# HW2.net
KiCad netlist of a schematic drawn in EAGLE
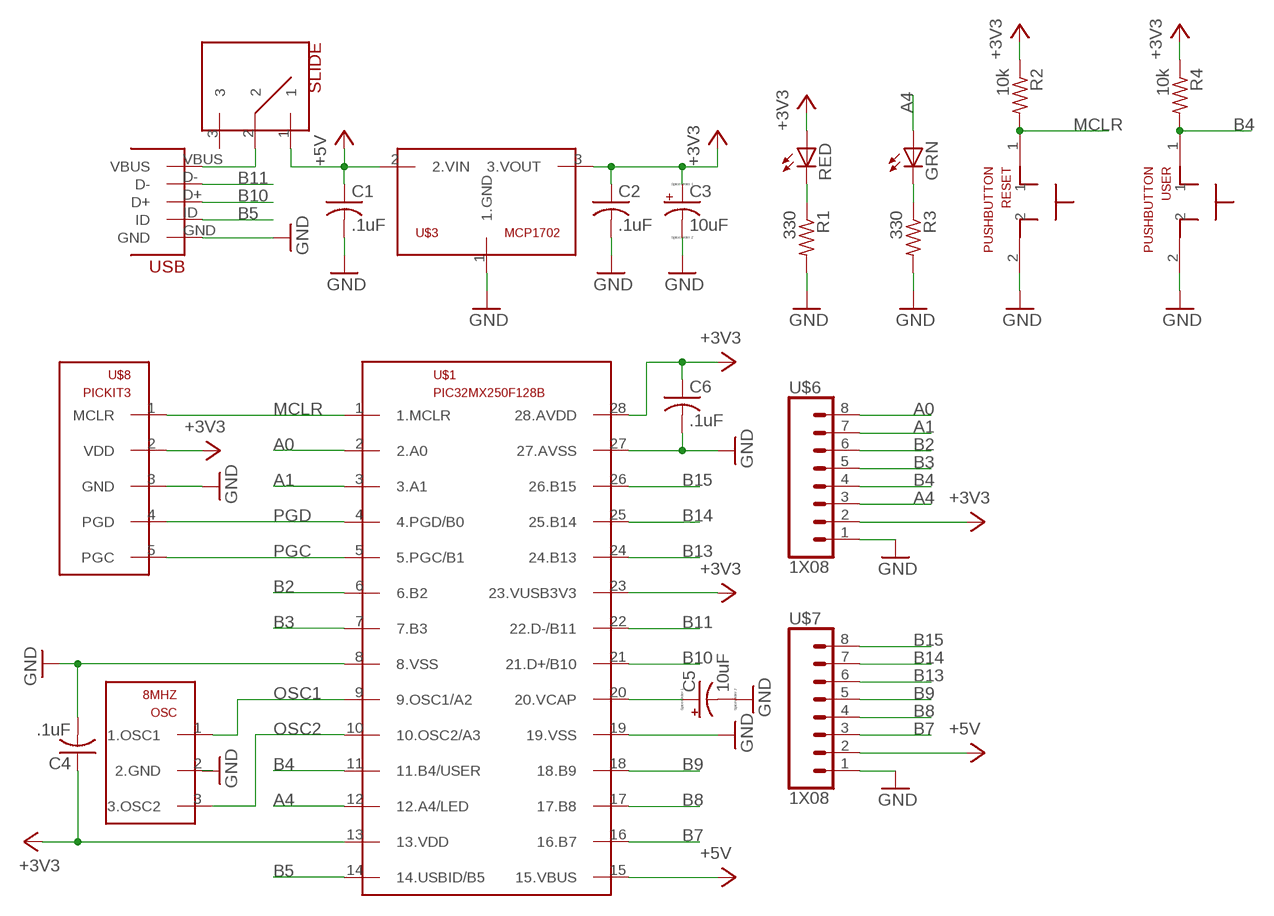
[diagram p0: schematic, sheet 1]

(export (version "E")
  (design (tool "Eeschema 10.0.6"))
  (components
    (comp (ref "8MHZ")
      (value "OSC")
      (footprint "eagle-import:OSC")
      (libsource (lib "eagle-import") (part "OSC"))
    )
    (comp (ref "C1")
      (value ".1uF")
      (footprint "eagle-import:C025-025X050")
      (libsource (lib "eagle-import") (part "C-US025-025X050"))
    )
    (comp (ref "C2")
      (value ".1uF")
      (footprint "eagle-import:C025-025X050")
      (libsource (lib "eagle-import") (part "C-US025-025X050"))
    )
    (comp (ref "C3")
      (value "10uF")
      (footprint "eagle-import:B45181B")
      (libsource (lib "eagle-import") (part "CPOL-USB45181B"))
    )
    (comp (ref "C4")
      (value ".1uF")
      (footprint "eagle-import:C025-025X050")
      (libsource (lib "eagle-import") (part "C-US025-025X050"))
    )
    (comp (ref "C5")
      (value "10uF")
      (footprint "eagle-import:B45181B")
      (libsource (lib "eagle-import") (part "CPOL-USB45181B"))
    )
    (comp (ref "C6")
      (value ".1uF")
      (footprint "eagle-import:C025-025X050")
      (libsource (lib "eagle-import") (part "C-US025-025X050"))
    )
    (comp (ref "GRN")
      (value "LED3MM")
      (footprint "eagle-import:LED3MM")
      (libsource (lib "eagle-import") (part "LED3MM"))
    )
    (comp (ref "R1")
      (value "330")
      (footprint "eagle-import:0207_10")
      (libsource (lib "eagle-import") (part "R-US_0207/10"))
    )
    (comp (ref "R2")
      (value "10k")
      (footprint "eagle-import:0207_10")
      (libsource (lib "eagle-import") (part "R-US_0207/10"))
    )
    (comp (ref "R3")
      (value "330")
      (footprint "eagle-import:0207_10")
      (libsource (lib "eagle-import") (part "R-US_0207/10"))
    )
    (comp (ref "R4")
      (value "10k")
      (footprint "eagle-import:0207_10")
      (libsource (lib "eagle-import") (part "R-US_0207/10"))
    )
    (comp (ref "RED")
      (value "LED3MM")
      (footprint "eagle-import:LED3MM")
      (libsource (lib "eagle-import") (part "LED3MM"))
    )
    (comp (ref "RESET")
      (value "PUSHBUTTON")
      (footprint "eagle-import:PUSHBUTTON")
      (libsource (lib "eagle-import") (part "PUSHBUTTON"))
    )
    (comp (ref "SLIDE")
      (value "SLIDESWITCH")
      (footprint "eagle-import:SLIDESWITCH")
      (libsource (lib "eagle-import") (part "SLIDESWITCH"))
    )
    (comp (ref "U$1")
      (value "PIC32MX250F128B")
      (footprint "eagle-import:DIL28-3")
      (libsource (lib "eagle-import") (part "PIC32MX250F128B"))
    )
    (comp (ref "U$3")
      (value "MCP1702")
      (footprint "eagle-import:TO92")
      (libsource (lib "eagle-import") (part "MCP1702"))
    )
    (comp (ref "U$5")
      (value "MINIUSB")
      (footprint "eagle-import:USB-MB-H")
      (libsource (lib "eagle-import") (part "MINIUSB"))
    )
    (comp (ref "U$6")
      (value "1X08")
      (footprint "eagle-import:CONN_08")
      (libsource (lib "eagle-import") (part "1X08"))
    )
    (comp (ref "U$7")
      (value "1X08")
      (footprint "eagle-import:CONN_08")
      (libsource (lib "eagle-import") (part "1X08"))
    )
    (comp (ref "U$8")
      (value "PICKIT3")
      (footprint "eagle-import:PICKIT3")
      (libsource (lib "eagle-import") (part "PICKIT3"))
    )
    (comp (ref "USER")
      (value "PUSHBUTTON")
      (footprint "eagle-import:PUSHBUTTON")
      (libsource (lib "eagle-import") (part "PUSHBUTTON"))
    )
  )
  (nets
    (net (code "1") (name "+3V3") (class "Default")
      (node (ref "C2") (pin "1") (pinfunction "1_1") (pintype "passive"))
      (node (ref "C3") (pin "+") (pinfunction "+_+") (pintype "passive"))
      (node (ref "C4") (pin "1") (pinfunction "1_1") (pintype "passive"))
      (node (ref "C6") (pin "1") (pinfunction "1_1") (pintype "passive"))
      (node (ref "R2") (pin "1") (pinfunction "1_1") (pintype "passive"))
      (node (ref "R4") (pin "1") (pinfunction "1_1") (pintype "passive"))
      (node (ref "RED") (pin "A") (pinfunction "A_A") (pintype "passive"))
      (node (ref "U$1") (pin "13") (pinfunction "13.VDD_13") (pintype "bidirectional"))
      (node (ref "U$1") (pin "23") (pinfunction "23.VUSB3V3_23") (pintype "bidirectional"))
      (node (ref "U$1") (pin "28") (pinfunction "28.AVDD_28") (pintype "bidirectional"))
      (node (ref "U$3") (pin "3") (pinfunction "3.VOUT_3") (pintype "bidirectional"))
      (node (ref "U$6") (pin "2") (pinfunction "2_2") (pintype "passive"))
      (node (ref "U$8") (pin "2") (pinfunction "VDD_2") (pintype "bidirectional"))
    )
    (net (code "2") (name "+5V") (class "Default")
      (node (ref "C1") (pin "1") (pinfunction "1_1") (pintype "passive"))
      (node (ref "SLIDE") (pin "1") (pinfunction "1_1") (pintype "bidirectional"))
      (node (ref "U$1") (pin "15") (pinfunction "15.VBUS_15") (pintype "bidirectional"))
      (node (ref "U$3") (pin "2") (pinfunction "2.VIN_2") (pintype "bidirectional"))
      (node (ref "U$7") (pin "2") (pinfunction "2_2") (pintype "passive"))
    )
    (net (code "3") (name "/A0") (class "Default")
      (node (ref "U$1") (pin "2") (pinfunction "2.A0_2") (pintype "bidirectional"))
      (node (ref "U$6") (pin "8") (pinfunction "8_8") (pintype "passive"))
    )
    (net (code "4") (name "/A1") (class "Default")
      (node (ref "U$1") (pin "3") (pinfunction "3.A1_3") (pintype "bidirectional"))
      (node (ref "U$6") (pin "7") (pinfunction "7_7") (pintype "passive"))
    )
    (net (code "5") (name "/A4") (class "Default")
      (node (ref "GRN") (pin "A") (pinfunction "A_A") (pintype "passive"))
      (node (ref "U$1") (pin "12") (pinfunction "12.A4/LED_12") (pintype "bidirectional"))
      (node (ref "U$6") (pin "3") (pinfunction "3_3") (pintype "passive"))
    )
    (net (code "6") (name "/B2") (class "Default")
      (node (ref "U$1") (pin "6") (pinfunction "6.B2_6") (pintype "bidirectional"))
      (node (ref "U$6") (pin "6") (pinfunction "6_6") (pintype "passive"))
    )
    (net (code "7") (name "/B3") (class "Default")
      (node (ref "U$1") (pin "7") (pinfunction "7.B3_7") (pintype "bidirectional"))
      (node (ref "U$6") (pin "5") (pinfunction "5_5") (pintype "passive"))
    )
    (net (code "8") (name "/B4") (class "Default")
      (node (ref "R4") (pin "2") (pinfunction "2_2") (pintype "passive"))
      (node (ref "U$1") (pin "11") (pinfunction "11.B4/USER_11") (pintype "bidirectional"))
      (node (ref "U$6") (pin "4") (pinfunction "4_4") (pintype "passive"))
      (node (ref "USER") (pin "1") (pinfunction "1_1") (pintype "bidirectional"))
    )
    (net (code "9") (name "/B5") (class "Default")
      (node (ref "U$1") (pin "14") (pinfunction "14.USBID/B5_14") (pintype "bidirectional"))
      (node (ref "U$5") (pin "ID") (pinfunction "ID_ID") (pintype "bidirectional"))
    )
    (net (code "10") (name "/B7") (class "Default")
      (node (ref "U$1") (pin "16") (pinfunction "16.B7_16") (pintype "bidirectional"))
      (node (ref "U$7") (pin "3") (pinfunction "3_3") (pintype "passive"))
    )
    (net (code "11") (name "/B8") (class "Default")
      (node (ref "U$1") (pin "17") (pinfunction "17.B8_17") (pintype "bidirectional"))
      (node (ref "U$7") (pin "4") (pinfunction "4_4") (pintype "passive"))
    )
    (net (code "12") (name "/B9") (class "Default")
      (node (ref "U$1") (pin "18") (pinfunction "18.B9_18") (pintype "bidirectional"))
      (node (ref "U$7") (pin "5") (pinfunction "5_5") (pintype "passive"))
    )
    (net (code "13") (name "/B10") (class "Default")
      (node (ref "U$1") (pin "21") (pinfunction "21.D+/B10_21") (pintype "bidirectional"))
      (node (ref "U$5") (pin "D+") (pinfunction "D+_D+") (pintype "bidirectional"))
    )
    (net (code "14") (name "/B11") (class "Default")
      (node (ref "U$1") (pin "22") (pinfunction "22.D-/B11_22") (pintype "bidirectional"))
      (node (ref "U$5") (pin "D-") (pinfunction "D-_D-") (pintype "bidirectional"))
    )
    (net (code "15") (name "/B13") (class "Default")
      (node (ref "U$1") (pin "24") (pinfunction "24.B13_24") (pintype "bidirectional"))
      (node (ref "U$7") (pin "6") (pinfunction "6_6") (pintype "passive"))
    )
    (net (code "16") (name "/B14") (class "Default")
      (node (ref "U$1") (pin "25") (pinfunction "25.B14_25") (pintype "bidirectional"))
      (node (ref "U$7") (pin "7") (pinfunction "7_7") (pintype "passive"))
    )
    (net (code "17") (name "/B15") (class "Default")
      (node (ref "U$1") (pin "26") (pinfunction "26.B15_26") (pintype "bidirectional"))
      (node (ref "U$7") (pin "8") (pinfunction "8_8") (pintype "passive"))
    )
    (net (code "18") (name "/MCLR") (class "Default")
      (node (ref "R2") (pin "2") (pinfunction "2_2") (pintype "passive"))
      (node (ref "RESET") (pin "1") (pinfunction "1_1") (pintype "bidirectional"))
      (node (ref "U$1") (pin "1") (pinfunction "1.MCLR_1") (pintype "bidirectional"))
      (node (ref "U$8") (pin "1") (pinfunction "MCLR_1") (pintype "bidirectional"))
    )
    (net (code "19") (name "/OSC1") (class "Default")
      (node (ref "8MHZ") (pin "1") (pinfunction "1.OSC1_1") (pintype "bidirectional"))
      (node (ref "U$1") (pin "9") (pinfunction "9.OSC1/A2_9") (pintype "bidirectional"))
    )
    (net (code "20") (name "/OSC2") (class "Default")
      (node (ref "8MHZ") (pin "3") (pinfunction "3.OSC2_3") (pintype "bidirectional"))
      (node (ref "U$1") (pin "10") (pinfunction "10.OSC2/A3_10") (pintype "bidirectional"))
    )
    (net (code "21") (name "/PGC") (class "Default")
      (node (ref "U$1") (pin "5") (pinfunction "5.PGC/B1_5") (pintype "bidirectional"))
      (node (ref "U$8") (pin "5") (pinfunction "PGC_5") (pintype "bidirectional"))
    )
    (net (code "22") (name "/PGD") (class "Default")
      (node (ref "U$1") (pin "4") (pinfunction "4.PGD/B0_4") (pintype "bidirectional"))
      (node (ref "U$8") (pin "4") (pinfunction "PGD_4") (pintype "bidirectional"))
    )
    (net (code "23") (name "GND") (class "Default")
      (node (ref "8MHZ") (pin "2") (pinfunction "2.GND_2") (pintype "bidirectional"))
      (node (ref "C1") (pin "2") (pinfunction "2_2") (pintype "passive"))
      (node (ref "C2") (pin "2") (pinfunction "2_2") (pintype "passive"))
      (node (ref "C3") (pin "-") (pinfunction "-_-") (pintype "passive"))
      (node (ref "C4") (pin "2") (pinfunction "2_2") (pintype "passive"))
      (node (ref "C5") (pin "-") (pinfunction "-_-") (pintype "passive"))
      (node (ref "C6") (pin "2") (pinfunction "2_2") (pintype "passive"))
      (node (ref "R1") (pin "2") (pinfunction "2_2") (pintype "passive"))
      (node (ref "R3") (pin "2") (pinfunction "2_2") (pintype "passive"))
      (node (ref "RESET") (pin "2") (pinfunction "2_2") (pintype "bidirectional"))
      (node (ref "U$1") (pin "19") (pinfunction "19.VSS_19") (pintype "bidirectional"))
      (node (ref "U$1") (pin "27") (pinfunction "27.AVSS_27") (pintype "bidirectional"))
      (node (ref "U$1") (pin "8") (pinfunction "8.VSS_8") (pintype "bidirectional"))
      (node (ref "U$3") (pin "1") (pinfunction "1.GND_1") (pintype "bidirectional"))
      (node (ref "U$5") (pin "GND") (pinfunction "GND_GND") (pintype "bidirectional"))
      (node (ref "U$6") (pin "1") (pinfunction "1_1") (pintype "passive"))
      (node (ref "U$7") (pin "1") (pinfunction "1_1") (pintype "passive"))
      (node (ref "U$8") (pin "3") (pinfunction "GND_3") (pintype "bidirectional"))
      (node (ref "USER") (pin "2") (pinfunction "2_2") (pintype "bidirectional"))
    )
    (net (code "24") (name "Net-(GRN-C)") (class "Default")
      (node (ref "GRN") (pin "K") (pinfunction "C_K") (pintype "passive"))
      (node (ref "R3") (pin "1") (pinfunction "1_1") (pintype "passive"))
    )
    (net (code "25") (name "Net-(RED-C)") (class "Default")
      (node (ref "R1") (pin "1") (pinfunction "1_1") (pintype "passive"))
      (node (ref "RED") (pin "K") (pinfunction "C_K") (pintype "passive"))
    )
    (net (code "26") (name "Net-(SLIDE-Pad2)") (class "Default")
      (node (ref "SLIDE") (pin "2") (pinfunction "2_2") (pintype "bidirectional"))
      (node (ref "U$5") (pin "VBUS") (pinfunction "VBUS_VBUS") (pintype "bidirectional"))
    )
    (net (code "27") (name "Net-(U$1-20.VCAP)") (class "Default")
      (node (ref "C5") (pin "+") (pinfunction "+_+") (pintype "passive"))
      (node (ref "U$1") (pin "20") (pinfunction "20.VCAP_20") (pintype "bidirectional"))
    )
    (net (code "28") (name "unconnected-(SLIDE-Pad3)") (class "Default")
      (node (ref "SLIDE") (pin "3") (pinfunction "3_3") (pintype "bidirectional"))
    )
  )
)
